# PAYL0007_GMSK_Modem_w_Proto.net
KiCad netlist of a schematic drawn in Altium Designer
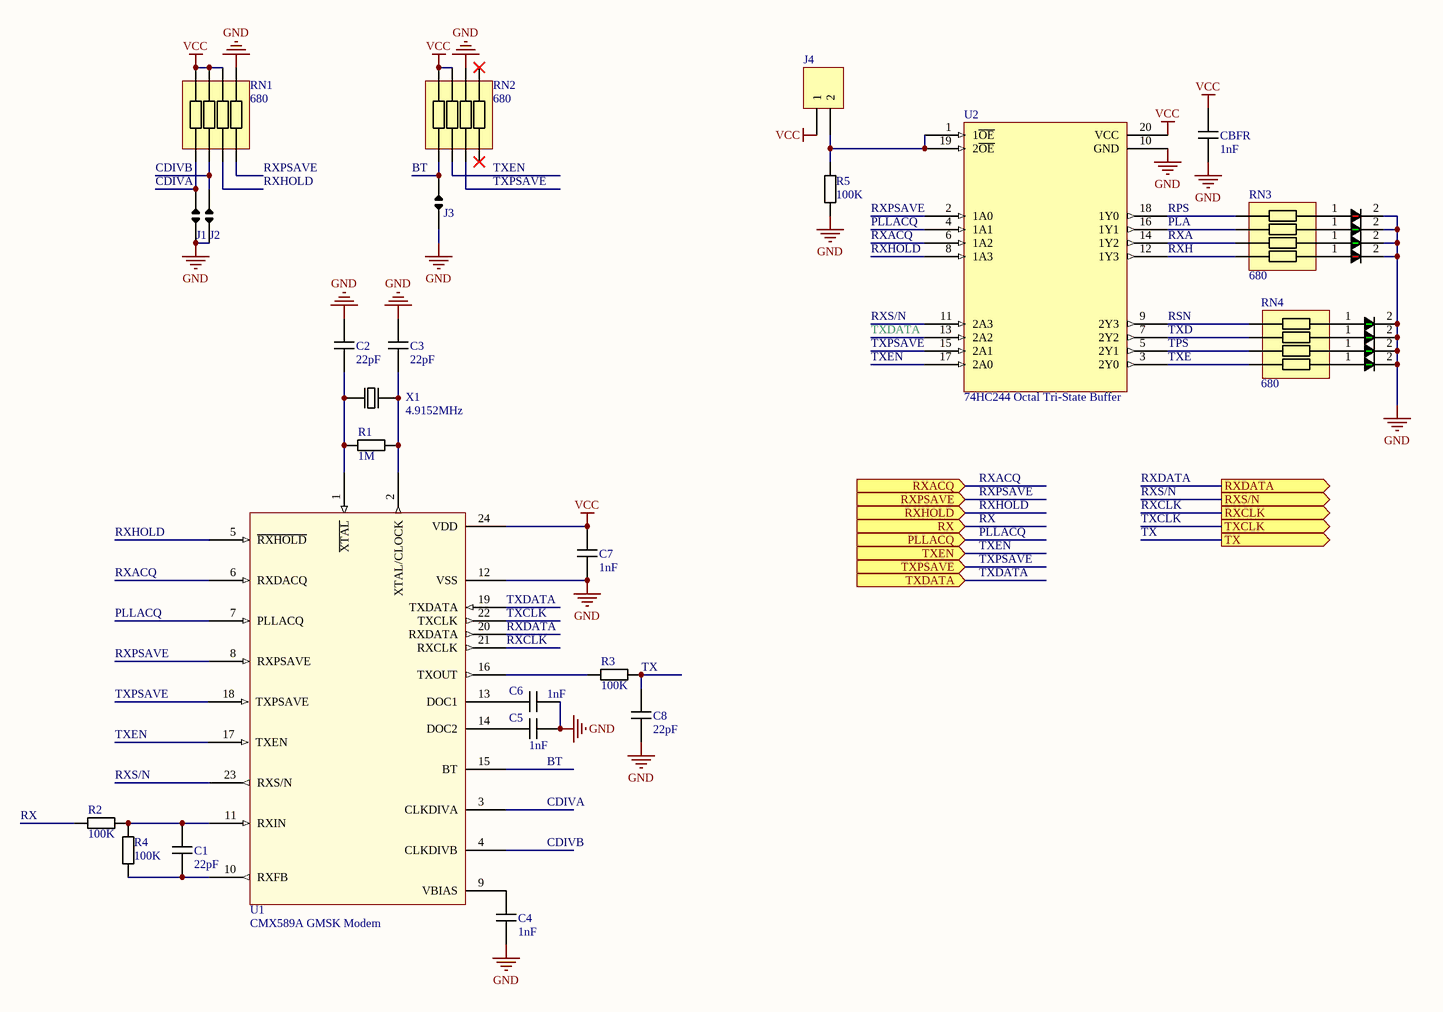
[diagram p0: PAYL0007 GMSK Modem w Proto.SchDoc]

(export (version "E")
  (design (tool "Eeschema 10.0.6"))
  (components
    (comp (ref "C1")
      (value "22pF")
      (footprint "0805 Cap")
      (description "0805 MLCC - NP0, 5%")
      (fields (field (name "Comment") "0805 Cap"))
      (libsource (lib "GMSK Prototyping Board") (part "0805 MLCC - NP0, 5%"))
    )
    (comp (ref "C2")
      (value "22pF")
      (footprint "0805 Cap")
      (description "0805 MLCC - NP0, 5%")
      (fields (field (name "Comment") "0805 Cap"))
      (libsource (lib "GMSK Prototyping Board") (part "0805 MLCC - NP0, 5%"))
    )
    (comp (ref "C3")
      (value "22pF")
      (footprint "0805 Cap")
      (description "0805 MLCC - NP0, 5%")
      (fields (field (name "Comment") "0805 Cap"))
      (libsource (lib "GMSK Prototyping Board") (part "0805 MLCC - NP0, 5%"))
    )
    (comp (ref "C4")
      (value "1nF")
      (footprint "0805 Cap")
      (description "0805 MLCC - X7R, 10%")
      (fields (field (name "Comment") "0805 Cap"))
      (libsource (lib "GMSK Prototyping Board") (part "0805 MLCC - X7R, 10%"))
    )
    (comp (ref "C5")
      (value "1nF")
      (footprint "0805 Cap")
      (description "0805 MLCC - X7R, 10%")
      (fields (field (name "Comment") "0805 Cap"))
      (libsource (lib "GMSK Prototyping Board") (part "0805 MLCC - X7R, 10%"))
    )
    (comp (ref "C6")
      (value "1nF")
      (footprint "0805 Cap")
      (description "0805 MLCC - X7R, 10%")
      (fields (field (name "Comment") "0805 Cap"))
      (libsource (lib "GMSK Prototyping Board") (part "0805 MLCC - X7R, 10%"))
    )
    (comp (ref "C7")
      (value "1nF")
      (footprint "0805 Cap")
      (description "0805 MLCC - X7R, 10%")
      (fields (field (name "Comment") "0805 Cap"))
      (libsource (lib "GMSK Prototyping Board") (part "0805 MLCC - X7R, 10%"))
    )
    (comp (ref "C8")
      (value "22pF")
      (footprint "0805 Cap")
      (description "0805 MLCC - NP0, 5%")
      (fields (field (name "Comment") "0805 Cap"))
      (libsource (lib "GMSK Prototyping Board") (part "0805 MLCC - NP0, 5%"))
    )
    (comp (ref "CBFR")
      (value "1nF")
      (footprint "0805 Cap")
      (description "0805 MLCC - X7R, 10%")
      (fields (field (name "Comment") "0805 Cap"))
      (libsource (lib "GMSK Prototyping Board") (part "0805 MLCC - X7R, 10%"))
    )
    (comp (ref "J1")
      (value "Jumper")
      (footprint "Solder Jumper C")
      (description "Solder Bridge")
      (libsource (lib "GMSK Prototyping Board") (part "Solder Bridge"))
    )
    (comp (ref "J2")
      (value "Jumper")
      (footprint "Solder Jumper C")
      (description "Solder Bridge")
      (libsource (lib "GMSK Prototyping Board") (part "Solder Bridge"))
    )
    (comp (ref "J3")
      (value "Jumper")
      (footprint "Solder Jumper C")
      (description "Solder Bridge")
      (libsource (lib "GMSK Prototyping Board") (part "Solder Bridge"))
    )
    (comp (ref "J4")
      (value "Header 2")
      (footprint "HDR1X2")
      (description "Header, 2-Pin")
      (fields (field (name "PUBLISHER") "Altium Limited"))
      (libsource (lib "GMSK Prototyping Board") (part "Header 2"))
    )
    (comp (ref "PLA1")
      (value "Green LED")
      (footprint "0603 LED")
      (description "Chip LED, Green, 0603 Footprint")
      (libsource (lib "GMSK Prototyping Board") (part "LED, SMD, GREEN"))
    )
    (comp (ref "R1")
      (value "1M")
      (footprint "0805 Resistor")
      (description "0805 Thin Film Resistor 0.1%")
      (fields (field (name "Comment") "0805 Resistor"))
      (libsource (lib "GMSK Prototyping Board") (part "0805 Thin Film Resistor 0.1%"))
    )
    (comp (ref "R2")
      (value "100K")
      (footprint "0805 Resistor")
      (description "0805 Thin Film Resistor 0.1%")
      (fields (field (name "Comment") "0805 Resistor"))
      (libsource (lib "GMSK Prototyping Board") (part "0805 Thin Film Resistor 0.1%"))
    )
    (comp (ref "R3")
      (value "100K")
      (footprint "0805 Resistor")
      (description "0805 Thin Film Resistor 0.1%")
      (fields (field (name "Comment") "0805 Resistor"))
      (libsource (lib "GMSK Prototyping Board") (part "0805 Thin Film Resistor 0.1%"))
    )
    (comp (ref "R4")
      (value "100K")
      (footprint "0805 Resistor")
      (description "0805 Thin Film Resistor 0.1%")
      (fields (field (name "Comment") "0805 Resistor"))
      (libsource (lib "") (part "0805 Thin Film Resistor 0.1%_2"))
    )
    (comp (ref "R5")
      (value "100K")
      (footprint "0805 Resistor")
      (description "0805 Thin Film Resistor 0.1%")
      (fields (field (name "Comment") "0805 Resistor"))
      (libsource (lib "") (part "0805 Thin Film Resistor 0.1%_1"))
    )
    (comp (ref "RN1")
      (value "680")
      (footprint "ACAS_0612_AC")
      (fields (field (name "Comment") "RN4"))
      (libsource (lib "") (part "RN4_2"))
    )
    (comp (ref "RN2")
      (value "680")
      (footprint "ACAS_0612_AC")
      (fields (field (name "Comment") "RN4"))
      (libsource (lib "GMSK Prototyping Board") (part "RN4"))
    )
    (comp (ref "RN3")
      (value "680")
      (footprint "ACAS_0612_AC")
      (fields (field (name "Comment") "RN4"))
      (libsource (lib "") (part "RN4_1"))
    )
    (comp (ref "RN4")
      (value "680")
      (footprint "ACAS_0612_AC")
      (fields (field (name "Comment") "RN4"))
      (libsource (lib "") (part "RN4_1"))
    )
    (comp (ref "RPS1")
      (value "Red LED")
      (footprint "0603 LED")
      (description "Chip LED, Red, 0603 Footprint")
      (libsource (lib "GMSK Prototyping Board") (part "LED, SMD, RED"))
    )
    (comp (ref "RSN1")
      (value "Green LED")
      (footprint "0603 LED")
      (description "Chip LED, Green, 0603 Footprint")
      (libsource (lib "GMSK Prototyping Board") (part "LED, SMD, GREEN"))
    )
    (comp (ref "RXA1")
      (value "Green LED")
      (footprint "0603 LED")
      (description "Chip LED, Green, 0603 Footprint")
      (libsource (lib "GMSK Prototyping Board") (part "LED, SMD, GREEN"))
    )
    (comp (ref "RXH1")
      (value "Red LED")
      (footprint "0603 LED")
      (description "Chip LED, Red, 0603 Footprint")
      (libsource (lib "GMSK Prototyping Board") (part "LED, SMD, RED"))
    )
    (comp (ref "TPS1")
      (value "Green LED")
      (footprint "0603 LED")
      (description "Chip LED, Green, 0603 Footprint")
      (libsource (lib "GMSK Prototyping Board") (part "LED, SMD, GREEN"))
    )
    (comp (ref "TXD1")
      (value "Green LED")
      (footprint "0603 LED")
      (description "Chip LED, Green, 0603 Footprint")
      (libsource (lib "GMSK Prototyping Board") (part "LED, SMD, GREEN"))
    )
    (comp (ref "TXE1")
      (value "Green LED")
      (footprint "0603 LED")
      (description "Chip LED, Green, 0603 Footprint")
      (libsource (lib "GMSK Prototyping Board") (part "LED, SMD, GREEN"))
    )
    (comp (ref "U1")
      (value "CMX589A GMSK Modem")
      (footprint "SOIC24 - GMSK MODEM")
      (libsource (lib "GMSK Prototyping Board") (part "CMX589A"))
    )
    (comp (ref "U2")
      (value "74HC244 Octal Tri-State Buffer")
      (footprint "SOIC20")
      (description "Octal Non-Inverting Three state buffer")
      (libsource (lib "GMSK Prototyping Board") (part "74HC244"))
    )
    (comp (ref "X1")
      (value "4.9152MHz")
      (footprint "HC49")
      (description "HC49 Crystal")
      (libsource (lib "GMSK Prototyping Board") (part "HC49 Crystal"))
    )
  )
  (nets
    (net (code "1") (name "/BT") (class "Default")
      (node (ref "J3") (pin "1") (pinfunction "1_1") (pintype "passive"))
      (node (ref "RN2") (pin "1") (pinfunction "1_1") (pintype "passive"))
      (node (ref "U1") (pin "15") (pinfunction "BT_15") (pintype "passive"))
    )
    (net (code "2") (name "/CDIVA") (class "Default")
      (node (ref "J1") (pin "2") (pinfunction "2_2") (pintype "passive"))
      (node (ref "RN1") (pin "5") (pinfunction "5_5") (pintype "passive"))
      (node (ref "U1") (pin "3") (pinfunction "CLKDIVA_3") (pintype "passive"))
    )
    (net (code "3") (name "/CDIVB") (class "Default")
      (node (ref "J2") (pin "1") (pinfunction "1_1") (pintype "passive"))
      (node (ref "RN1") (pin "6") (pinfunction "6_6") (pintype "passive"))
      (node (ref "U1") (pin "4") (pinfunction "CLKDIVB_4") (pintype "passive"))
    )
    (net (code "4") (name "/PLA") (class "Default")
      (node (ref "RN3") (pin "6") (pinfunction "6_6") (pintype "passive"))
      (node (ref "U2") (pin "16") (pinfunction "1Y1_16") (pintype "output"))
    )
    (net (code "5") (name "/PLLACQ") (class "Default")
      (node (ref "U1") (pin "7") (pinfunction "PLLACQ_7") (pintype "input"))
      (node (ref "U2") (pin "4") (pinfunction "1A1_4") (pintype "input"))
    )
    (net (code "6") (name "/RPS") (class "Default")
      (node (ref "RN3") (pin "5") (pinfunction "5_5") (pintype "passive"))
      (node (ref "U2") (pin "18") (pinfunction "1Y0_18") (pintype "output"))
    )
    (net (code "7") (name "/RSN") (class "Default")
      (node (ref "RN4") (pin "5") (pinfunction "5_5") (pintype "passive"))
      (node (ref "U2") (pin "9") (pinfunction "2Y3_9") (pintype "output"))
    )
    (net (code "8") (name "/RX") (class "Default")
      (node (ref "R2") (pin "1") (pinfunction "1_1") (pintype "passive"))
    )
    (net (code "9") (name "/RXA") (class "Default")
      (node (ref "RN3") (pin "7") (pinfunction "7_7") (pintype "passive"))
      (node (ref "U2") (pin "14") (pinfunction "1Y2_14") (pintype "output"))
    )
    (net (code "10") (name "/RXACQ") (class "Default")
      (node (ref "U1") (pin "6") (pinfunction "RXDACQ_6") (pintype "input"))
      (node (ref "U2") (pin "6") (pinfunction "1A2_6") (pintype "input"))
    )
    (net (code "11") (name "/RXCLK") (class "Default")
      (node (ref "U1") (pin "21") (pinfunction "RXCLK_21") (pintype "output"))
    )
    (net (code "12") (name "/RXDATA") (class "Default")
      (node (ref "U1") (pin "20") (pinfunction "RXDATA_20") (pintype "output"))
    )
    (net (code "13") (name "/RXH") (class "Default")
      (node (ref "RN3") (pin "8") (pinfunction "8_8") (pintype "passive"))
      (node (ref "U2") (pin "12") (pinfunction "1Y3_12") (pintype "output"))
    )
    (net (code "14") (name "/RXHOLD") (class "Default")
      (node (ref "RN1") (pin "7") (pinfunction "7_7") (pintype "passive"))
      (node (ref "U1") (pin "5") (pinfunction "~{RXHOLD}_5") (pintype "input"))
      (node (ref "U2") (pin "8") (pinfunction "1A3_8") (pintype "input"))
    )
    (net (code "15") (name "/RXPSAVE") (class "Default")
      (node (ref "RN1") (pin "8") (pinfunction "8_8") (pintype "passive"))
      (node (ref "U1") (pin "8") (pinfunction "RXPSAVE_8") (pintype "input"))
      (node (ref "U2") (pin "2") (pinfunction "1A0_2") (pintype "input"))
    )
    (net (code "16") (name "/RXS{slash}N") (class "Default")
      (node (ref "U1") (pin "23") (pinfunction "RXS/N_23") (pintype "output"))
      (node (ref "U2") (pin "11") (pinfunction "2A3_11") (pintype "input"))
    )
    (net (code "17") (name "/TPS") (class "Default")
      (node (ref "RN4") (pin "7") (pinfunction "7_7") (pintype "passive"))
      (node (ref "U2") (pin "5") (pinfunction "2Y1_5") (pintype "output"))
    )
    (net (code "18") (name "/TX") (class "Default")
      (node (ref "C8") (pin "1") (pinfunction "1_1") (pintype "passive"))
      (node (ref "R3") (pin "2") (pinfunction "2_2") (pintype "passive"))
    )
    (net (code "19") (name "/TXCLK") (class "Default")
      (node (ref "U1") (pin "22") (pinfunction "TXCLK_22") (pintype "output"))
    )
    (net (code "20") (name "/TXD") (class "Default")
      (node (ref "RN4") (pin "6") (pinfunction "6_6") (pintype "passive"))
      (node (ref "U2") (pin "7") (pinfunction "2Y2_7") (pintype "output"))
    )
    (net (code "21") (name "/TXDATA") (class "Default")
      (node (ref "U1") (pin "19") (pinfunction "TXDATA_19") (pintype "input"))
      (node (ref "U2") (pin "13") (pinfunction "2A2_13") (pintype "input"))
    )
    (net (code "22") (name "/TXE") (class "Default")
      (node (ref "RN4") (pin "8") (pinfunction "8_8") (pintype "passive"))
      (node (ref "U2") (pin "3") (pinfunction "2Y0_3") (pintype "output"))
    )
    (net (code "23") (name "/TXEN") (class "Default")
      (node (ref "RN2") (pin "2") (pinfunction "2_2") (pintype "passive"))
      (node (ref "U1") (pin "17") (pinfunction "TXEN_17") (pintype "input"))
      (node (ref "U2") (pin "17") (pinfunction "2A0_17") (pintype "input"))
    )
    (net (code "24") (name "/TXPSAVE") (class "Default")
      (node (ref "RN2") (pin "3") (pinfunction "3_3") (pintype "passive"))
      (node (ref "U1") (pin "18") (pinfunction "TXPSAVE_18") (pintype "input"))
      (node (ref "U2") (pin "15") (pinfunction "2A1_15") (pintype "input"))
    )
    (net (code "25") (name "GND") (class "Default")
      (node (ref "C2") (pin "2") (pinfunction "2_2") (pintype "passive"))
      (node (ref "C3") (pin "2") (pinfunction "2_2") (pintype "passive"))
      (node (ref "C4") (pin "2") (pinfunction "2_2") (pintype "passive"))
      (node (ref "C5") (pin "2") (pinfunction "2_2") (pintype "passive"))
      (node (ref "C6") (pin "1") (pinfunction "1_1") (pintype "passive"))
      (node (ref "C7") (pin "2") (pinfunction "2_2") (pintype "passive"))
      (node (ref "C8") (pin "2") (pinfunction "2_2") (pintype "passive"))
      (node (ref "CBFR") (pin "1") (pinfunction "1_1") (pintype "passive"))
      (node (ref "J1") (pin "1") (pinfunction "1_1") (pintype "passive"))
      (node (ref "J2") (pin "2") (pinfunction "2_2") (pintype "passive"))
      (node (ref "J3") (pin "2") (pinfunction "2_2") (pintype "passive"))
      (node (ref "PLA1") (pin "2") (pinfunction "2_2") (pintype "passive"))
      (node (ref "R5") (pin "1") (pinfunction "1_1") (pintype "passive"))
      (node (ref "RN1") (pin "1") (pinfunction "1_1") (pintype "passive"))
      (node (ref "RN2") (pin "6") (pinfunction "6_6") (pintype "passive"))
      (node (ref "RPS1") (pin "2") (pinfunction "2_2") (pintype "passive"))
      (node (ref "RSN1") (pin "2") (pinfunction "2_2") (pintype "passive"))
      (node (ref "RXA1") (pin "2") (pinfunction "2_2") (pintype "passive"))
      (node (ref "RXH1") (pin "2") (pinfunction "2_2") (pintype "passive"))
      (node (ref "TPS1") (pin "2") (pinfunction "2_2") (pintype "passive"))
      (node (ref "TXD1") (pin "2") (pinfunction "2_2") (pintype "passive"))
      (node (ref "TXE1") (pin "2") (pinfunction "2_2") (pintype "passive"))
      (node (ref "U1") (pin "12") (pinfunction "VSS_12") (pintype "power_in"))
      (node (ref "U2") (pin "10") (pinfunction "GND_10") (pintype "passive"))
    )
    (net (code "26") (name "Net-(PLA1-Pad1)") (class "Default")
      (node (ref "PLA1") (pin "1") (pinfunction "1_1") (pintype "passive"))
      (node (ref "RN3") (pin "3") (pinfunction "3_3") (pintype "passive"))
    )
    (net (code "27") (name "Net-(RN3-Pad1)") (class "Default")
      (node (ref "RN3") (pin "1") (pinfunction "1_1") (pintype "passive"))
      (node (ref "RXH1") (pin "1") (pinfunction "1_1") (pintype "passive"))
    )
    (net (code "28") (name "Net-(RN3-Pad2)") (class "Default")
      (node (ref "RN3") (pin "2") (pinfunction "2_2") (pintype "passive"))
      (node (ref "RXA1") (pin "1") (pinfunction "1_1") (pintype "passive"))
    )
    (net (code "29") (name "Net-(RN3-Pad4)") (class "Default")
      (node (ref "RN3") (pin "4") (pinfunction "4_4") (pintype "passive"))
      (node (ref "RPS1") (pin "1") (pinfunction "1_1") (pintype "passive"))
    )
    (net (code "30") (name "Net-(RN4-Pad1)") (class "Default")
      (node (ref "RN4") (pin "1") (pinfunction "1_1") (pintype "passive"))
      (node (ref "TXE1") (pin "1") (pinfunction "1_1") (pintype "passive"))
    )
    (net (code "31") (name "Net-(RN4-Pad2)") (class "Default")
      (node (ref "RN4") (pin "2") (pinfunction "2_2") (pintype "passive"))
      (node (ref "TPS1") (pin "1") (pinfunction "1_1") (pintype "passive"))
    )
    (net (code "32") (name "Net-(RN4-Pad3)") (class "Default")
      (node (ref "RN4") (pin "3") (pinfunction "3_3") (pintype "passive"))
      (node (ref "TXD1") (pin "1") (pinfunction "1_1") (pintype "passive"))
    )
    (net (code "33") (name "Net-(RN4-Pad4)") (class "Default")
      (node (ref "RN4") (pin "4") (pinfunction "4_4") (pintype "passive"))
      (node (ref "RSN1") (pin "1") (pinfunction "1_1") (pintype "passive"))
    )
    (net (code "34") (name "Net-(U1-DOC1)") (class "Default")
      (node (ref "C6") (pin "2") (pinfunction "2_2") (pintype "passive"))
      (node (ref "U1") (pin "13") (pinfunction "DOC1_13") (pintype "passive"))
    )
    (net (code "35") (name "Net-(U1-DOC2)") (class "Default")
      (node (ref "C5") (pin "1") (pinfunction "1_1") (pintype "passive"))
      (node (ref "U1") (pin "14") (pinfunction "DOC2_14") (pintype "passive"))
    )
    (net (code "36") (name "Net-(U1-RXFB)") (class "Default")
      (node (ref "C1") (pin "1") (pinfunction "1_1") (pintype "passive"))
      (node (ref "R4") (pin "2") (pinfunction "2_2") (pintype "passive"))
      (node (ref "U1") (pin "10") (pinfunction "RXFB_10") (pintype "output"))
    )
    (net (code "37") (name "Net-(U1-RXIN)") (class "Default")
      (node (ref "C1") (pin "2") (pinfunction "2_2") (pintype "passive"))
      (node (ref "R2") (pin "2") (pinfunction "2_2") (pintype "passive"))
      (node (ref "R4") (pin "1") (pinfunction "1_1") (pintype "passive"))
      (node (ref "U1") (pin "11") (pinfunction "RXIN_11") (pintype "input"))
    )
    (net (code "38") (name "Net-(U1-TXOUT)") (class "Default")
      (node (ref "R3") (pin "1") (pinfunction "1_1") (pintype "passive"))
      (node (ref "U1") (pin "16") (pinfunction "TXOUT_16") (pintype "output"))
    )
    (net (code "39") (name "Net-(U1-VBIAS)") (class "Default")
      (node (ref "C4") (pin "1") (pinfunction "1_1") (pintype "passive"))
      (node (ref "U1") (pin "9") (pinfunction "VBIAS_9") (pintype "passive"))
    )
    (net (code "40") (name "Net-(U1-XTAL{slash}CLOCK)") (class "Default")
      (node (ref "C3") (pin "1") (pinfunction "1_1") (pintype "passive"))
      (node (ref "R1") (pin "2") (pinfunction "2_2") (pintype "passive"))
      (node (ref "U1") (pin "2") (pinfunction "XTAL/CLOCK_2") (pintype "output"))
      (node (ref "X1") (pin "2") (pinfunction "2_2") (pintype "passive"))
    )
    (net (code "41") (name "Net-(U1-~{XTAL})") (class "Default")
      (node (ref "C2") (pin "1") (pinfunction "1_1") (pintype "passive"))
      (node (ref "R1") (pin "1") (pinfunction "1_1") (pintype "passive"))
      (node (ref "U1") (pin "1") (pinfunction "~{XTAL}_1") (pintype "input"))
      (node (ref "X1") (pin "1") (pinfunction "1_1") (pintype "passive"))
    )
    (net (code "42") (name "Net-(U2-1~{OE})") (class "Default")
      (node (ref "J4") (pin "2") (pinfunction "2_2") (pintype "passive"))
      (node (ref "R5") (pin "2") (pinfunction "2_2") (pintype "passive"))
      (node (ref "U2") (pin "1") (pinfunction "1~{OE}_1") (pintype "input"))
      (node (ref "U2") (pin "19") (pinfunction "2~{OE}_19") (pintype "input"))
    )
    (net (code "43") (name "VCC") (class "Default")
      (node (ref "C7") (pin "1") (pinfunction "1_1") (pintype "passive"))
      (node (ref "CBFR") (pin "2") (pinfunction "2_2") (pintype "passive"))
      (node (ref "J4") (pin "1") (pinfunction "1_1") (pintype "passive"))
      (node (ref "RN1") (pin "2") (pinfunction "2_2") (pintype "passive"))
      (node (ref "RN1") (pin "3") (pinfunction "3_3") (pintype "passive"))
      (node (ref "RN1") (pin "4") (pinfunction "4_4") (pintype "passive"))
      (node (ref "RN2") (pin "7") (pinfunction "7_7") (pintype "passive"))
      (node (ref "RN2") (pin "8") (pinfunction "8_8") (pintype "passive"))
      (node (ref "U1") (pin "24") (pinfunction "VDD_24") (pintype "power_in"))
      (node (ref "U2") (pin "20") (pinfunction "VCC_20") (pintype "passive"))
    )
    (net (code "44") (name "unconnected-(RN2-Pad4)") (class "Default")
      (node (ref "RN2") (pin "4") (pinfunction "4_4") (pintype "passive+no_connect"))
    )
    (net (code "45") (name "unconnected-(RN2-Pad5)") (class "Default")
      (node (ref "RN2") (pin "5") (pinfunction "5_5") (pintype "passive+no_connect"))
    )
  )
)
